# untitled.net
KiCad netlist of a schematic drawn in EAGLE
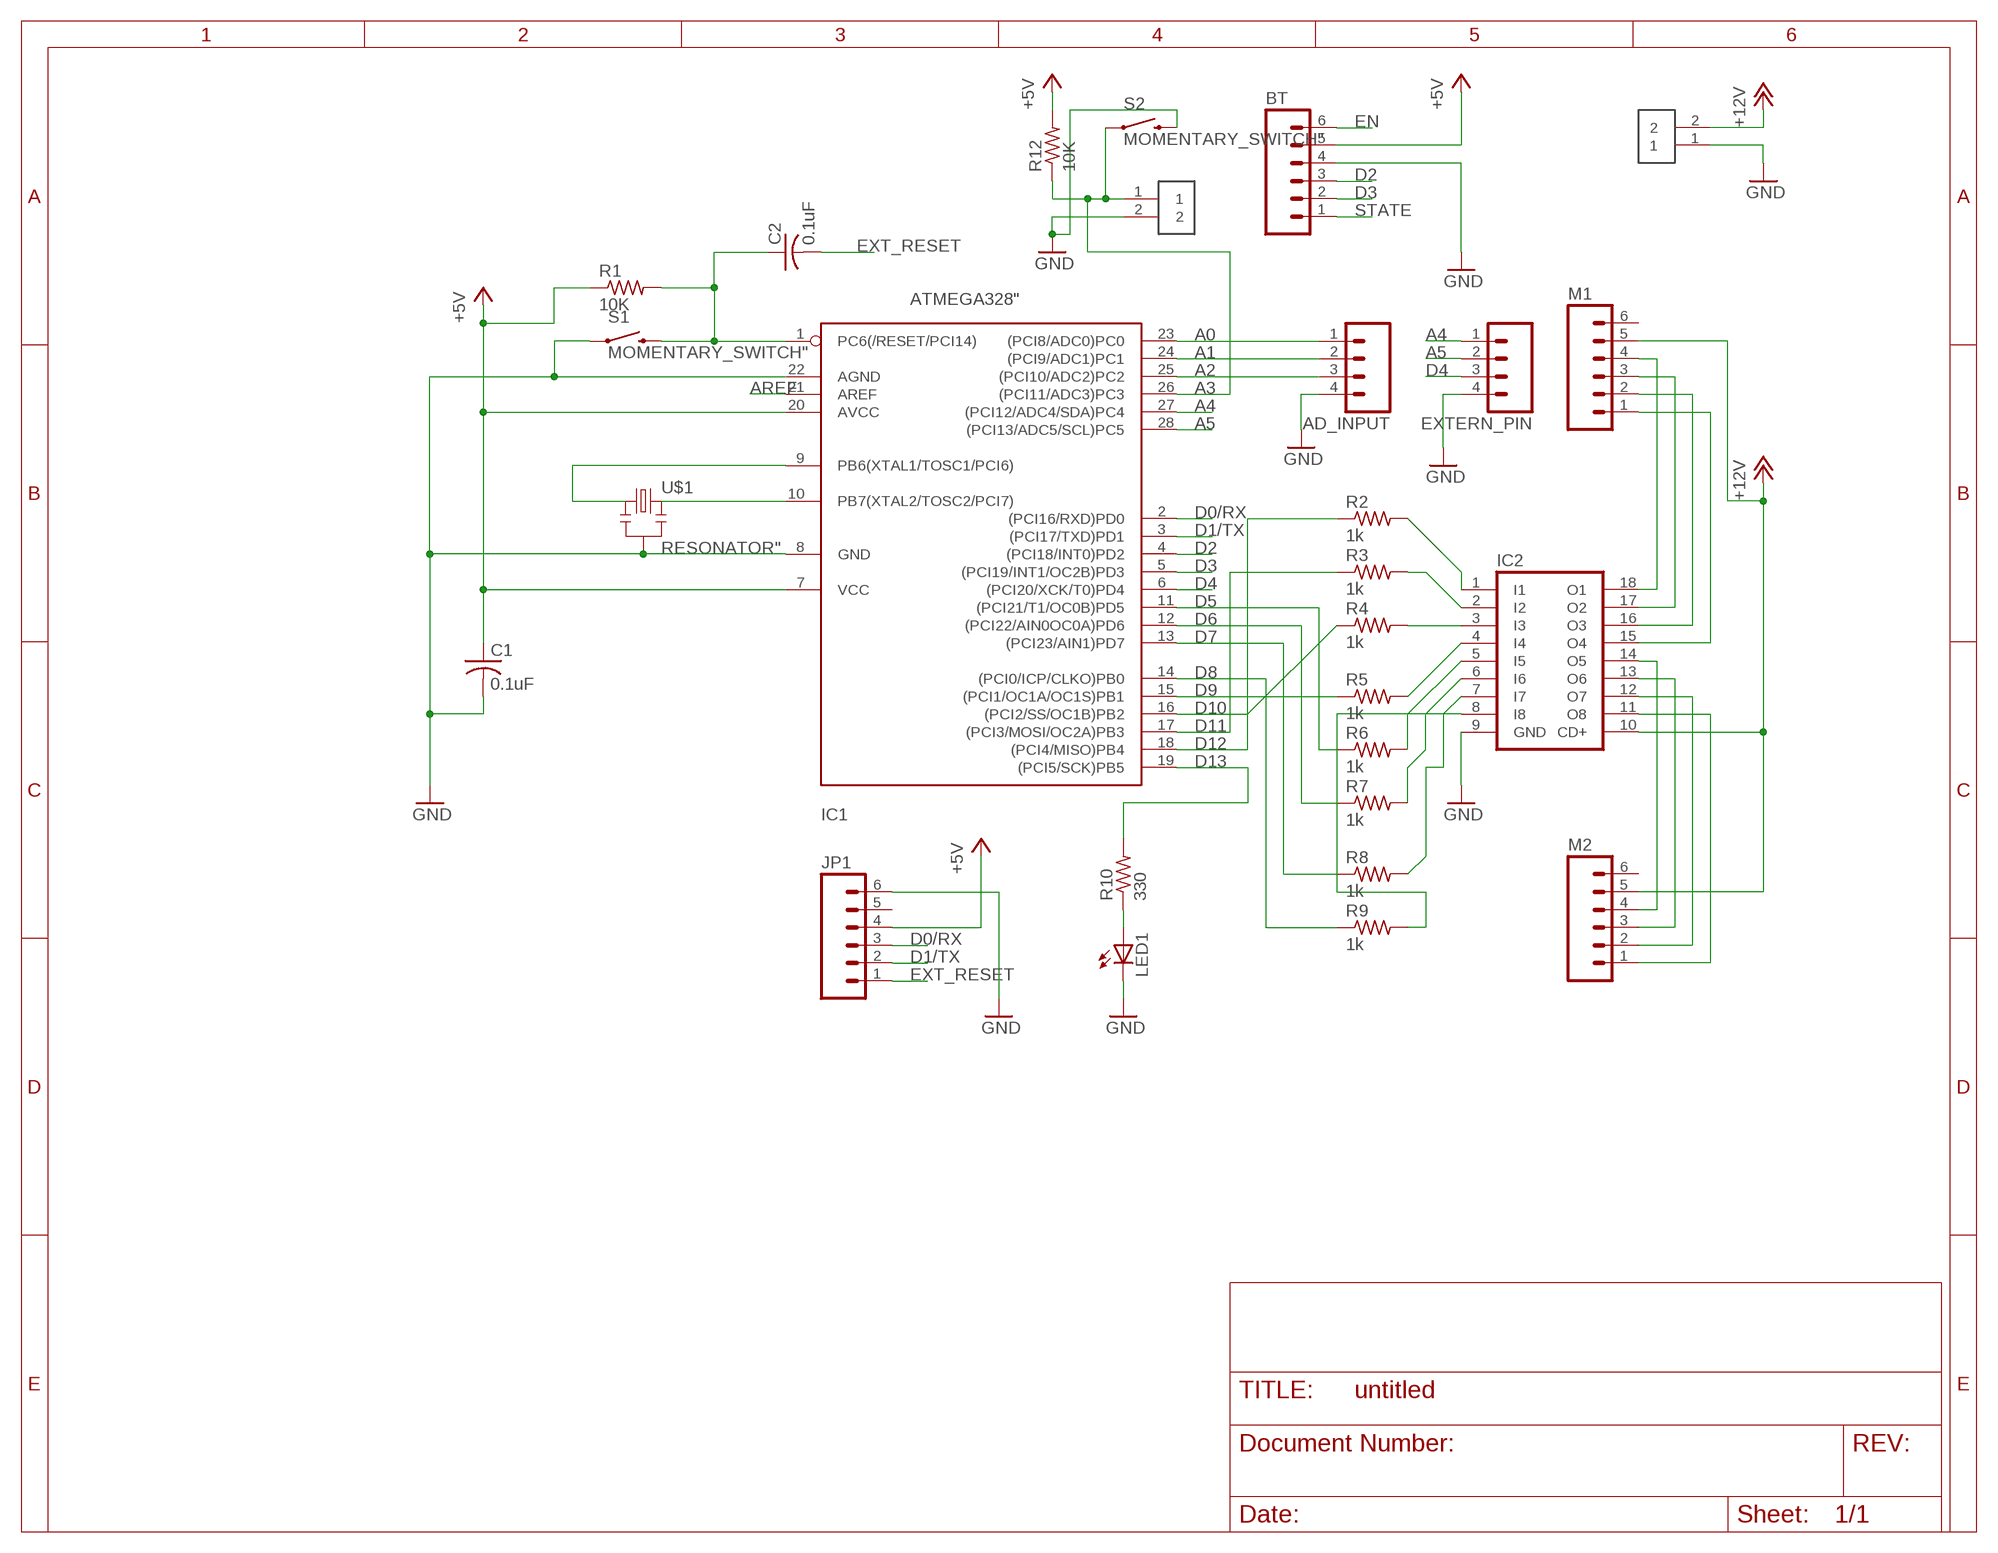
[diagram p0: schematic, sheet 1]

(export (version "E")
  (design (tool "Eeschema 10.0.6"))
  (components
    (comp (ref "12V_INPUT")
      (value "1X02_HEADER")
      (footprint "eagle-import:1X02_HEADER")
      (libsource (lib "eagle-import") (part "1X02_HEADER"))
    )
    (comp (ref "AD_INPUT")
      (value "1X04_HEADER\"")
      (footprint "eagle-import:1X04_HEADER")
      (libsource (lib "eagle-import") (part "1X04_HEADER{dblquote}"))
    )
    (comp (ref "BT")
      (value "1X06_HEADER\"")
      (footprint "eagle-import:1X06_HEADER")
      (libsource (lib "eagle-import") (part "1X06_HEADER{dblquote}"))
    )
    (comp (ref "C1")
      (value "0.1uF")
      (footprint "eagle-import:UNPOLARIZED_CAP")
      (libsource (lib "eagle-import") (part "UNPOLARIZED_CAP{dblquote}"))
    )
    (comp (ref "C2")
      (value "0.1uF")
      (footprint "eagle-import:UNPOLARIZED_CAP")
      (libsource (lib "eagle-import") (part "UNPOLARIZED_CAP{dblquote}"))
    )
    (comp (ref "EXTERN_PIN")
      (value "1X04_HEADER\"")
      (footprint "eagle-import:1X04_HEADER")
      (libsource (lib "eagle-import") (part "1X04_HEADER{dblquote}"))
    )
    (comp (ref "IC1")
      (value "ATMEGA328\"")
      (footprint "eagle-import:ATMEGA328")
      (libsource (lib "eagle-import") (part "ATMEGA328{dblquote}"))
    )
    (comp (ref "IC2")
      (value "ULN2803A")
      (footprint "eagle-import:DIL18")
      (libsource (lib "eagle-import") (part "ULN2803A"))
    )
    (comp (ref "JP1")
      (value "1X06_HEADER\"")
      (footprint "eagle-import:1X06_HEADER")
      (libsource (lib "eagle-import") (part "1X06_HEADER{dblquote}"))
    )
    (comp (ref "LED1")
      (value "LED3MM")
      (footprint "eagle-import:LED")
      (libsource (lib "eagle-import") (part "LED3MM"))
    )
    (comp (ref "LIMIT_SW")
      (value "1X02_HEADER")
      (footprint "eagle-import:1X02_HEADER")
      (libsource (lib "eagle-import") (part "1X02_HEADER"))
    )
    (comp (ref "M1")
      (value "1X06_HEADER\"")
      (footprint "eagle-import:1X06_HEADER")
      (libsource (lib "eagle-import") (part "1X06_HEADER{dblquote}"))
    )
    (comp (ref "M2")
      (value "1X06_HEADER\"")
      (footprint "eagle-import:1X06_HEADER")
      (libsource (lib "eagle-import") (part "1X06_HEADER{dblquote}"))
    )
    (comp (ref "R1")
      (value "10K")
      (footprint "eagle-import:RESISTOR")
      (libsource (lib "eagle-import") (part "RESISTOR1/6WATT"))
    )
    (comp (ref "R2")
      (value "1k")
      (footprint "eagle-import:RESISTOR")
      (libsource (lib "eagle-import") (part "RESISTOR1/6WATT"))
    )
    (comp (ref "R3")
      (value "1k")
      (footprint "eagle-import:RESISTOR")
      (libsource (lib "eagle-import") (part "RESISTOR1/6WATT"))
    )
    (comp (ref "R4")
      (value "1k")
      (footprint "eagle-import:RESISTOR")
      (libsource (lib "eagle-import") (part "RESISTOR1/6WATT"))
    )
    (comp (ref "R5")
      (value "1k")
      (footprint "eagle-import:RESISTOR")
      (libsource (lib "eagle-import") (part "RESISTOR1/6WATT"))
    )
    (comp (ref "R6")
      (value "1k")
      (footprint "eagle-import:RESISTOR")
      (libsource (lib "eagle-import") (part "RESISTOR1/6WATT"))
    )
    (comp (ref "R7")
      (value "1k")
      (footprint "eagle-import:RESISTOR")
      (libsource (lib "eagle-import") (part "RESISTOR1/6WATT"))
    )
    (comp (ref "R8")
      (value "1k")
      (footprint "eagle-import:RESISTOR")
      (libsource (lib "eagle-import") (part "RESISTOR1/6WATT"))
    )
    (comp (ref "R9")
      (value "1k")
      (footprint "eagle-import:RESISTOR")
      (libsource (lib "eagle-import") (part "RESISTOR1/6WATT"))
    )
    (comp (ref "R10")
      (value "330")
      (footprint "eagle-import:RESISTOR")
      (libsource (lib "eagle-import") (part "RESISTOR1/6WATT"))
    )
    (comp (ref "R12")
      (value "10K")
      (footprint "eagle-import:RESISTOR")
      (libsource (lib "eagle-import") (part "RESISTOR1/6WATT"))
    )
    (comp (ref "S1")
      (value "MOMENTARY_SWITCH\"")
      (footprint "eagle-import:MOMENTARY_SWITCH")
      (libsource (lib "eagle-import") (part "MOMENTARY_SWITCH{dblquote}"))
    )
    (comp (ref "S2")
      (value "MOMENTARY_SWITCH\"")
      (footprint "eagle-import:MOMENTARY_SWITCH")
      (libsource (lib "eagle-import") (part "MOMENTARY_SWITCH{dblquote}"))
    )
    (comp (ref "U$1")
      (value "RESONATOR\"")
      (footprint "eagle-import:RESONATOR")
      (libsource (lib "eagle-import") (part "RESONATOR{dblquote}"))
    )
  )
  (nets
    (net (code "1") (name "+5V") (class "Default")
      (node (ref "BT") (pin "5") (pinfunction "5_5") (pintype "passive"))
      (node (ref "C1") (pin "1") (pinfunction "1_1") (pintype "passive"))
      (node (ref "IC1") (pin "20") (pinfunction "AVCC_20") (pintype "bidirectional"))
      (node (ref "IC1") (pin "7") (pinfunction "VCC_7") (pintype "bidirectional"))
      (node (ref "JP1") (pin "4") (pinfunction "4_4") (pintype "passive"))
      (node (ref "R1") (pin "1") (pinfunction "1_1") (pintype "passive"))
      (node (ref "R12") (pin "2") (pinfunction "2_2") (pintype "passive"))
    )
    (net (code "2") (name "+12V") (class "Default")
      (node (ref "12V_INPUT") (pin "2") (pinfunction "2_2") (pintype "bidirectional"))
      (node (ref "IC2") (pin "10") (pinfunction "CD+_10") (pintype "passive"))
      (node (ref "M1") (pin "5") (pinfunction "5_5") (pintype "passive"))
      (node (ref "M2") (pin "5") (pinfunction "5_5") (pintype "passive"))
    )
    (net (code "3") (name "/A0") (class "Default")
      (node (ref "AD_INPUT") (pin "1") (pinfunction "1_1") (pintype "passive"))
      (node (ref "IC1") (pin "23") (pinfunction "(PCI8/ADC0)PC0_23") (pintype "bidirectional"))
    )
    (net (code "4") (name "/A1") (class "Default")
      (node (ref "AD_INPUT") (pin "2") (pinfunction "2_2") (pintype "passive"))
      (node (ref "IC1") (pin "24") (pinfunction "(PCI9/ADC1)PC1_24") (pintype "bidirectional"))
    )
    (net (code "5") (name "/A2") (class "Default")
      (node (ref "AD_INPUT") (pin "3") (pinfunction "3_3") (pintype "passive"))
      (node (ref "IC1") (pin "25") (pinfunction "(PCI10/ADC2)PC2_25") (pintype "bidirectional"))
    )
    (net (code "6") (name "/A3") (class "Default")
      (node (ref "IC1") (pin "26") (pinfunction "(PCI11/ADC3)PC3_26") (pintype "bidirectional"))
      (node (ref "LIMIT_SW") (pin "1") (pinfunction "1_1") (pintype "bidirectional"))
      (node (ref "R12") (pin "1") (pinfunction "1_1") (pintype "passive"))
      (node (ref "S2") (pin "1") (pinfunction "1_1") (pintype "passive"))
    )
    (net (code "7") (name "/A4") (class "Default")
      (node (ref "EXTERN_PIN") (pin "1") (pinfunction "1_1") (pintype "passive"))
      (node (ref "IC1") (pin "27") (pinfunction "(PCI12/ADC4/SDA)PC4_27") (pintype "bidirectional"))
    )
    (net (code "8") (name "/A5") (class "Default")
      (node (ref "EXTERN_PIN") (pin "2") (pinfunction "2_2") (pintype "passive"))
      (node (ref "IC1") (pin "28") (pinfunction "(PCI13/ADC5/SCL)PC5_28") (pintype "bidirectional"))
    )
    (net (code "9") (name "/AREF") (class "Default")
      (node (ref "IC1") (pin "21") (pinfunction "AREF_21") (pintype "bidirectional"))
    )
    (net (code "10") (name "/D0{slash}RX") (class "Default")
      (node (ref "IC1") (pin "2") (pinfunction "(PCI16/RXD)PD0_2") (pintype "bidirectional"))
      (node (ref "JP1") (pin "3") (pinfunction "3_3") (pintype "passive"))
    )
    (net (code "11") (name "/D1{slash}TX") (class "Default")
      (node (ref "IC1") (pin "3") (pinfunction "(PCI17/TXD)PD1_3") (pintype "bidirectional"))
      (node (ref "JP1") (pin "2") (pinfunction "2_2") (pintype "passive"))
    )
    (net (code "12") (name "/D2") (class "Default")
      (node (ref "BT") (pin "3") (pinfunction "3_3") (pintype "passive"))
      (node (ref "IC1") (pin "4") (pinfunction "(PCI18/INT0)PD2_4") (pintype "bidirectional"))
    )
    (net (code "13") (name "/D3") (class "Default")
      (node (ref "BT") (pin "2") (pinfunction "2_2") (pintype "passive"))
      (node (ref "IC1") (pin "5") (pinfunction "(PCI19/INT1/OC2B)PD3_5") (pintype "bidirectional"))
    )
    (net (code "14") (name "/D4") (class "Default")
      (node (ref "EXTERN_PIN") (pin "3") (pinfunction "3_3") (pintype "passive"))
      (node (ref "IC1") (pin "6") (pinfunction "(PCI20/XCK/T0)PD4_6") (pintype "bidirectional"))
    )
    (net (code "15") (name "/D5") (class "Default")
      (node (ref "IC1") (pin "11") (pinfunction "(PCI21/T1/OC0B)PD5_11") (pintype "bidirectional"))
      (node (ref "R6") (pin "1") (pinfunction "1_1") (pintype "passive"))
    )
    (net (code "16") (name "/D6") (class "Default")
      (node (ref "IC1") (pin "12") (pinfunction "(PCI22/AIN0OC0A)PD6_12") (pintype "bidirectional"))
      (node (ref "R7") (pin "1") (pinfunction "1_1") (pintype "passive"))
    )
    (net (code "17") (name "/D7") (class "Default")
      (node (ref "IC1") (pin "13") (pinfunction "(PCI23/AIN1)PD7_13") (pintype "bidirectional"))
      (node (ref "R8") (pin "1") (pinfunction "1_1") (pintype "passive"))
    )
    (net (code "18") (name "/D8") (class "Default")
      (node (ref "IC1") (pin "14") (pinfunction "(PCI0/ICP/CLKO)PB0_14") (pintype "bidirectional"))
      (node (ref "R9") (pin "1") (pinfunction "1_1") (pintype "passive"))
    )
    (net (code "19") (name "/D9") (class "Default")
      (node (ref "IC1") (pin "15") (pinfunction "(PCI1/OC1A/OC1S)PB1_15") (pintype "bidirectional"))
      (node (ref "R5") (pin "1") (pinfunction "1_1") (pintype "passive"))
    )
    (net (code "20") (name "/D10") (class "Default")
      (node (ref "IC1") (pin "16") (pinfunction "(PCI2/SS/OC1B)PB2_16") (pintype "bidirectional"))
      (node (ref "R4") (pin "1") (pinfunction "1_1") (pintype "passive"))
    )
    (net (code "21") (name "/D11") (class "Default")
      (node (ref "IC1") (pin "17") (pinfunction "(PCI3/MOSI/OC2A)PB3_17") (pintype "bidirectional"))
      (node (ref "R3") (pin "1") (pinfunction "1_1") (pintype "passive"))
    )
    (net (code "22") (name "/D12") (class "Default")
      (node (ref "IC1") (pin "18") (pinfunction "(PCI4/MISO)PB4_18") (pintype "bidirectional"))
      (node (ref "R2") (pin "1") (pinfunction "1_1") (pintype "passive"))
    )
    (net (code "23") (name "/D13") (class "Default")
      (node (ref "IC1") (pin "19") (pinfunction "(PCI5/SCK)PB5_19") (pintype "bidirectional"))
      (node (ref "R10") (pin "2") (pinfunction "2_2") (pintype "passive"))
    )
    (net (code "24") (name "/EN") (class "Default")
      (node (ref "BT") (pin "6") (pinfunction "6_6") (pintype "passive"))
    )
    (net (code "25") (name "/EXT_RESET") (class "Default")
      (node (ref "C2") (pin "2") (pinfunction "2_2") (pintype "passive"))
      (node (ref "JP1") (pin "1") (pinfunction "1_1") (pintype "passive"))
    )
    (net (code "26") (name "/STATE") (class "Default")
      (node (ref "BT") (pin "1") (pinfunction "1_1") (pintype "passive"))
    )
    (net (code "27") (name "GND") (class "Default")
      (node (ref "12V_INPUT") (pin "1") (pinfunction "1_1") (pintype "bidirectional"))
      (node (ref "AD_INPUT") (pin "4") (pinfunction "4_4") (pintype "passive"))
      (node (ref "BT") (pin "4") (pinfunction "4_4") (pintype "passive"))
      (node (ref "C1") (pin "2") (pinfunction "2_2") (pintype "passive"))
      (node (ref "EXTERN_PIN") (pin "4") (pinfunction "4_4") (pintype "passive"))
      (node (ref "IC1") (pin "22") (pinfunction "AGND_22") (pintype "bidirectional"))
      (node (ref "IC1") (pin "8") (pinfunction "GND_8") (pintype "bidirectional"))
      (node (ref "IC2") (pin "9") (pinfunction "GND_9") (pintype "power_in"))
      (node (ref "JP1") (pin "6") (pinfunction "6_6") (pintype "passive"))
      (node (ref "LED1") (pin "K") (pinfunction "C_K") (pintype "passive"))
      (node (ref "LIMIT_SW") (pin "2") (pinfunction "2_2") (pintype "bidirectional"))
      (node (ref "S1") (pin "1") (pinfunction "1_1") (pintype "passive"))
      (node (ref "S2") (pin "3") (pinfunction "2_3") (pintype "passive"))
      (node (ref "U$1") (pin "2") (pinfunction "2_2") (pintype "passive"))
    )
    (net (code "28") (name "Net-(IC1-PB6(XTAL1{slash}TOSC1{slash}PCI6))") (class "Default")
      (node (ref "IC1") (pin "9") (pinfunction "PB6(XTAL1/TOSC1/PCI6)_9") (pintype "bidirectional"))
      (node (ref "U$1") (pin "1") (pinfunction "1_1") (pintype "passive"))
    )
    (net (code "29") (name "Net-(IC1-PB7(XTAL2{slash}TOSC2{slash}PCI7))") (class "Default")
      (node (ref "IC1") (pin "10") (pinfunction "PB7(XTAL2/TOSC2/PCI7)_10") (pintype "bidirectional"))
      (node (ref "U$1") (pin "3") (pinfunction "3_3") (pintype "passive"))
    )
    (net (code "30") (name "Net-(IC1-PC6({slash}RESET{slash}PCI14))") (class "Default")
      (node (ref "C2") (pin "1") (pinfunction "1_1") (pintype "passive"))
      (node (ref "IC1") (pin "1") (pinfunction "PC6(/RESET/PCI14)_1") (pintype "bidirectional"))
      (node (ref "R1") (pin "2") (pinfunction "2_2") (pintype "passive"))
      (node (ref "S1") (pin "3") (pinfunction "2_3") (pintype "passive"))
    )
    (net (code "31") (name "Net-(IC2-I1)") (class "Default")
      (node (ref "IC2") (pin "1") (pinfunction "I1_1") (pintype "input"))
      (node (ref "R2") (pin "2") (pinfunction "2_2") (pintype "passive"))
    )
    (net (code "32") (name "Net-(IC2-I2)") (class "Default")
      (node (ref "IC2") (pin "2") (pinfunction "I2_2") (pintype "input"))
      (node (ref "R3") (pin "2") (pinfunction "2_2") (pintype "passive"))
    )
    (net (code "33") (name "Net-(IC2-I3)") (class "Default")
      (node (ref "IC2") (pin "3") (pinfunction "I3_3") (pintype "input"))
      (node (ref "R4") (pin "2") (pinfunction "2_2") (pintype "passive"))
    )
    (net (code "34") (name "Net-(IC2-I4)") (class "Default")
      (node (ref "IC2") (pin "4") (pinfunction "I4_4") (pintype "input"))
      (node (ref "R5") (pin "2") (pinfunction "2_2") (pintype "passive"))
    )
    (net (code "35") (name "Net-(IC2-I5)") (class "Default")
      (node (ref "IC2") (pin "5") (pinfunction "I5_5") (pintype "input"))
      (node (ref "R6") (pin "2") (pinfunction "2_2") (pintype "passive"))
    )
    (net (code "36") (name "Net-(IC2-I6)") (class "Default")
      (node (ref "IC2") (pin "6") (pinfunction "I6_6") (pintype "input"))
      (node (ref "R7") (pin "2") (pinfunction "2_2") (pintype "passive"))
    )
    (net (code "37") (name "Net-(IC2-I7)") (class "Default")
      (node (ref "IC2") (pin "7") (pinfunction "I7_7") (pintype "input"))
      (node (ref "R8") (pin "2") (pinfunction "2_2") (pintype "passive"))
    )
    (net (code "38") (name "Net-(IC2-I8)") (class "Default")
      (node (ref "IC2") (pin "8") (pinfunction "I8_8") (pintype "input"))
      (node (ref "R9") (pin "2") (pinfunction "2_2") (pintype "passive"))
    )
    (net (code "39") (name "Net-(IC2-O1)") (class "Default")
      (node (ref "IC2") (pin "18") (pinfunction "O1_18") (pintype "open_collector"))
      (node (ref "M1") (pin "4") (pinfunction "4_4") (pintype "passive"))
    )
    (net (code "40") (name "Net-(IC2-O2)") (class "Default")
      (node (ref "IC2") (pin "17") (pinfunction "O2_17") (pintype "open_collector"))
      (node (ref "M1") (pin "3") (pinfunction "3_3") (pintype "passive"))
    )
    (net (code "41") (name "Net-(IC2-O3)") (class "Default")
      (node (ref "IC2") (pin "16") (pinfunction "O3_16") (pintype "open_collector"))
      (node (ref "M1") (pin "2") (pinfunction "2_2") (pintype "passive"))
    )
    (net (code "42") (name "Net-(IC2-O4)") (class "Default")
      (node (ref "IC2") (pin "15") (pinfunction "O4_15") (pintype "open_collector"))
      (node (ref "M1") (pin "1") (pinfunction "1_1") (pintype "passive"))
    )
    (net (code "43") (name "Net-(IC2-O5)") (class "Default")
      (node (ref "IC2") (pin "14") (pinfunction "O5_14") (pintype "open_collector"))
      (node (ref "M2") (pin "4") (pinfunction "4_4") (pintype "passive"))
    )
    (net (code "44") (name "Net-(IC2-O6)") (class "Default")
      (node (ref "IC2") (pin "13") (pinfunction "O6_13") (pintype "open_collector"))
      (node (ref "M2") (pin "3") (pinfunction "3_3") (pintype "passive"))
    )
    (net (code "45") (name "Net-(IC2-O7)") (class "Default")
      (node (ref "IC2") (pin "12") (pinfunction "O7_12") (pintype "open_collector"))
      (node (ref "M2") (pin "2") (pinfunction "2_2") (pintype "passive"))
    )
    (net (code "46") (name "Net-(IC2-O8)") (class "Default")
      (node (ref "IC2") (pin "11") (pinfunction "O8_11") (pintype "open_collector"))
      (node (ref "M2") (pin "1") (pinfunction "1_1") (pintype "passive"))
    )
    (net (code "47") (name "Net-(LED1-PadA)") (class "Default")
      (node (ref "LED1") (pin "A") (pinfunction "A_A") (pintype "passive"))
      (node (ref "R10") (pin "1") (pinfunction "1_1") (pintype "passive"))
    )
    (net (code "48") (name "unconnected-(JP1-Pad5)") (class "Default")
      (node (ref "JP1") (pin "5") (pinfunction "5_5") (pintype "passive"))
    )
    (net (code "49") (name "unconnected-(M1-Pad6)") (class "Default")
      (node (ref "M1") (pin "6") (pinfunction "6_6") (pintype "passive"))
    )
    (net (code "50") (name "unconnected-(M2-Pad6)") (class "Default")
      (node (ref "M2") (pin "6") (pinfunction "6_6") (pintype "passive"))
    )
  )
)
